# AM-Crystal-RX-LM324.net
KiCad netlist of a schematic drawn in EAGLE
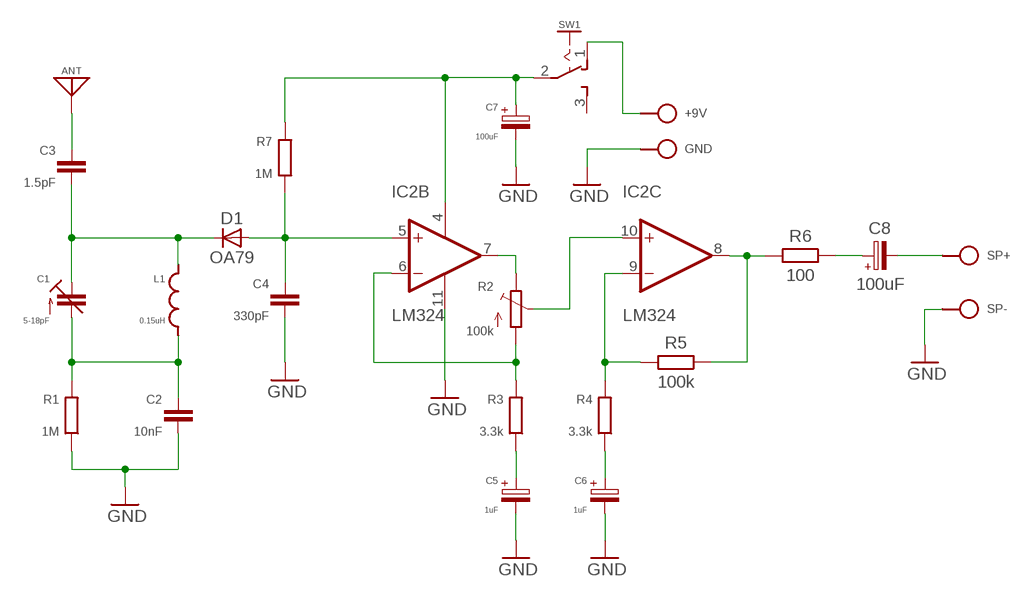
[diagram p0: schematic, sheet 1]

(export (version "E")
  (design (tool "Eeschema 10.0.6"))
  (components
    (comp (ref "+9V")
      (value "BAT+")
      (footprint "eagle-import:SPAD")
      (libsource (lib "eagle-import") (part "SPAD"))
    )
    (comp (ref "ANT")
      (value "ANT")
      (footprint "eagle-import:SPAD")
      (libsource (lib "eagle-import") (part "ANT"))
    )
    (comp (ref "C1")
      (value "5-18pF")
      (footprint "eagle-import:TRIM-2222-808")
      (libsource (lib "eagle-import") (part "C-TR-PH201272222-808-2PIN"))
    )
    (comp (ref "C2")
      (value "10nF")
      (footprint "eagle-import:C050-025X075_V")
      (libsource (lib "eagle-import") (part "C050-025X075/V"))
    )
    (comp (ref "C3")
      (value "1.5pF")
      (footprint "eagle-import:C050-020X036")
      (libsource (lib "eagle-import") (part "C050-020X036"))
    )
    (comp (ref "C4")
      (value "330pF")
      (footprint "eagle-import:C050-024X044_V")
      (libsource (lib "eagle-import") (part "C050-024X044/V"))
    )
    (comp (ref "C5")
      (value "1uF")
      (footprint "eagle-import:E2.5-4_V")
      (libsource (lib "eagle-import") (part "CPOLE2,5-4/V"))
    )
    (comp (ref "C6")
      (value "1uF")
      (footprint "eagle-import:E2,5-3")
      (libsource (lib "eagle-import") (part "CPOLE2,5-3"))
    )
    (comp (ref "C7")
      (value "100uF")
      (footprint "eagle-import:E5-5_V")
      (libsource (lib "eagle-import") (part "CPOLE5-5/V"))
    )
    (comp (ref "C8")
      (value "100uF")
      (footprint "eagle-import:E2,5-5_V")
      (libsource (lib "eagle-import") (part "CPOLE2,5-5/V"))
    )
    (comp (ref "D1")
      (value "OA79")
      (footprint "eagle-import:OA79-18_V")
      (libsource (lib "eagle-import") (part "OA7918/V"))
    )
    (comp (ref "GND")
      (value "BAT-")
      (footprint "eagle-import:SPAD")
      (libsource (lib "eagle-import") (part "SPAD"))
    )
    (comp (ref "IC2")
      (value "LM324")
      (footprint "eagle-import:DIL14")
      (libsource (lib "eagle-import") (part "LM324N"))
    )
    (comp (ref "L1")
      (value "0.15uH")
      (footprint "eagle-import:L-04-5_5")
      (libsource (lib "eagle-import") (part "L-SHORT04-5/5"))
    )
    (comp (ref "R1")
      (value "1M")
      (footprint "eagle-import:0202_7-V")
      (libsource (lib "eagle-import") (part "R0202/7-V"))
    )
    (comp (ref "R2")
      (value "100k")
      (footprint "eagle-import:B64Y")
      (libsource (lib "eagle-import") (part "TRIM"))
    )
    (comp (ref "R3")
      (value "3.3k")
      (footprint "eagle-import:0202_7")
      (libsource (lib "eagle-import") (part "R0202/7"))
    )
    (comp (ref "R4")
      (value "3.3k")
      (footprint "eagle-import:0202_7-V")
      (libsource (lib "eagle-import") (part "R0202/7-V"))
    )
    (comp (ref "R5")
      (value "100k")
      (footprint "eagle-import:0202_7-V")
      (libsource (lib "eagle-import") (part "R0202/7-V"))
    )
    (comp (ref "R6")
      (value "100")
      (footprint "eagle-import:0202_7-V")
      (libsource (lib "eagle-import") (part "R0202/7-V"))
    )
    (comp (ref "R7")
      (value "1M")
      (footprint "eagle-import:0202_7-V")
      (libsource (lib "eagle-import") (part "R0202/7-V"))
    )
    (comp (ref "SP+")
      (value "SPKR+")
      (footprint "eagle-import:SPAD")
      (libsource (lib "eagle-import") (part "SPAD"))
    )
    (comp (ref "SP-")
      (value "SPKR-")
      (footprint "eagle-import:SPAD")
      (libsource (lib "eagle-import") (part "SPAD"))
    )
    (comp (ref "SW1")
      (value "SL-SW-1P-2T-H")
      (footprint "eagle-import:SLSW-1P2T-H")
      (libsource (lib "eagle-import") (part "SL-SW-1P-2T-H"))
    )
  )
  (nets
    (net (code "1") (name "GND") (class "Default")
      (node (ref "C2") (pin "2") (pinfunction "2_2") (pintype "passive"))
      (node (ref "C4") (pin "2") (pinfunction "2_2") (pintype "passive"))
      (node (ref "C5") (pin "-") (pinfunction "-_-") (pintype "passive"))
      (node (ref "C6") (pin "-") (pinfunction "-_-") (pintype "passive"))
      (node (ref "C7") (pin "-") (pinfunction "-_-") (pintype "passive"))
      (node (ref "GND") (pin "1") (pinfunction "P$1_1") (pintype "bidirectional"))
      (node (ref "IC2") (pin "11") (pinfunction "V-_11") (pintype "power_in"))
      (node (ref "R1") (pin "1") (pinfunction "1_1") (pintype "passive"))
      (node (ref "SP-") (pin "1") (pinfunction "P$1_1") (pintype "bidirectional"))
    )
    (net (code "2") (name "Net-(+9V-P$1)") (class "Default")
      (node (ref "+9V") (pin "1") (pinfunction "P$1_1") (pintype "bidirectional"))
      (node (ref "SW1") (pin "1") (pinfunction "O_1") (pintype "passive"))
    )
    (net (code "3") (name "Net-(ANT-Pad1)") (class "Default")
      (node (ref "ANT") (pin "1") (pinfunction "1_1") (pintype "output"))
      (node (ref "C3") (pin "1") (pinfunction "1_1") (pintype "passive"))
    )
    (net (code "4") (name "Net-(C1-A)") (class "Default")
      (node (ref "C1") (pin "1") (pinfunction "A_1") (pintype "passive"))
      (node (ref "C2") (pin "1") (pinfunction "1_1") (pintype "passive"))
      (node (ref "L1") (pin "1") (pinfunction "1_1") (pintype "passive"))
      (node (ref "R1") (pin "2") (pinfunction "2_2") (pintype "passive"))
    )
    (net (code "5") (name "Net-(C1-E)") (class "Default")
      (node (ref "C1") (pin "2") (pinfunction "E_2") (pintype "passive"))
      (node (ref "C3") (pin "2") (pinfunction "2_2") (pintype "passive"))
      (node (ref "D1") (pin "C") (pinfunction "C_C") (pintype "passive"))
      (node (ref "L1") (pin "2") (pinfunction "2_2") (pintype "passive"))
    )
    (net (code "6") (name "Net-(C5-Pad+)") (class "Default")
      (node (ref "C5") (pin "+") (pinfunction "+_+") (pintype "passive"))
      (node (ref "R3") (pin "1") (pinfunction "1_1") (pintype "passive"))
    )
    (net (code "7") (name "Net-(C6-Pad+)") (class "Default")
      (node (ref "C6") (pin "+") (pinfunction "+_+") (pintype "passive"))
      (node (ref "R4") (pin "1") (pinfunction "1_1") (pintype "passive"))
    )
    (net (code "8") (name "Net-(C8-Pad+)") (class "Default")
      (node (ref "C8") (pin "+") (pinfunction "+_+") (pintype "passive"))
      (node (ref "R6") (pin "1") (pinfunction "1_1") (pintype "passive"))
    )
    (net (code "9") (name "Net-(IC2B-+IN)") (class "Default")
      (node (ref "C4") (pin "1") (pinfunction "1_1") (pintype "passive"))
      (node (ref "D1") (pin "A") (pinfunction "A_A") (pintype "passive"))
      (node (ref "IC2") (pin "5") (pinfunction "+IN_5") (pintype "input"))
      (node (ref "R7") (pin "1") (pinfunction "1_1") (pintype "passive"))
    )
    (net (code "10") (name "Net-(IC2B--IN)") (class "Default")
      (node (ref "IC2") (pin "6") (pinfunction "-IN_6") (pintype "input"))
      (node (ref "R2") (pin "A") (pinfunction "A_A") (pintype "passive"))
      (node (ref "R3") (pin "2") (pinfunction "2_2") (pintype "passive"))
    )
    (net (code "11") (name "Net-(IC2B-OUT)") (class "Default")
      (node (ref "IC2") (pin "7") (pinfunction "OUT_7") (pintype "output"))
      (node (ref "R2") (pin "E") (pinfunction "E_E") (pintype "passive"))
    )
    (net (code "12") (name "Net-(IC2C-+IN)") (class "Default")
      (node (ref "IC2") (pin "10") (pinfunction "+IN_10") (pintype "input"))
      (node (ref "R2") (pin "S") (pinfunction "S_S") (pintype "passive"))
    )
    (net (code "13") (name "Net-(IC2C--IN)") (class "Default")
      (node (ref "IC2") (pin "9") (pinfunction "-IN_9") (pintype "input"))
      (node (ref "R4") (pin "2") (pinfunction "2_2") (pintype "passive"))
      (node (ref "R5") (pin "2") (pinfunction "2_2") (pintype "passive"))
    )
    (net (code "14") (name "Net-(IC2C-OUT)") (class "Default")
      (node (ref "IC2") (pin "8") (pinfunction "OUT_8") (pintype "output"))
      (node (ref "R5") (pin "1") (pinfunction "1_1") (pintype "passive"))
      (node (ref "R6") (pin "2") (pinfunction "2_2") (pintype "passive"))
    )
    (net (code "15") (name "Net-(IC2E-V+)") (class "Default")
      (node (ref "C7") (pin "+") (pinfunction "+_+") (pintype "passive"))
      (node (ref "IC2") (pin "4") (pinfunction "V+_4") (pintype "power_in"))
      (node (ref "R7") (pin "2") (pinfunction "2_2") (pintype "passive"))
      (node (ref "SW1") (pin "2") (pinfunction "P_2") (pintype "passive"))
    )
    (net (code "16") (name "Net-(SP+-P$1)") (class "Default")
      (node (ref "C8") (pin "-") (pinfunction "-_-") (pintype "passive"))
      (node (ref "SP+") (pin "1") (pinfunction "P$1_1") (pintype "bidirectional"))
    )
    (net (code "17") (name "unconnected-(SW1-S-Pad3)") (class "Default")
      (node (ref "SW1") (pin "3") (pinfunction "S_3") (pintype "passive"))
    )
  )
)
